# IED_GR_Module_Rev_01.net
KiCad netlist of a schematic drawn in EAGLE
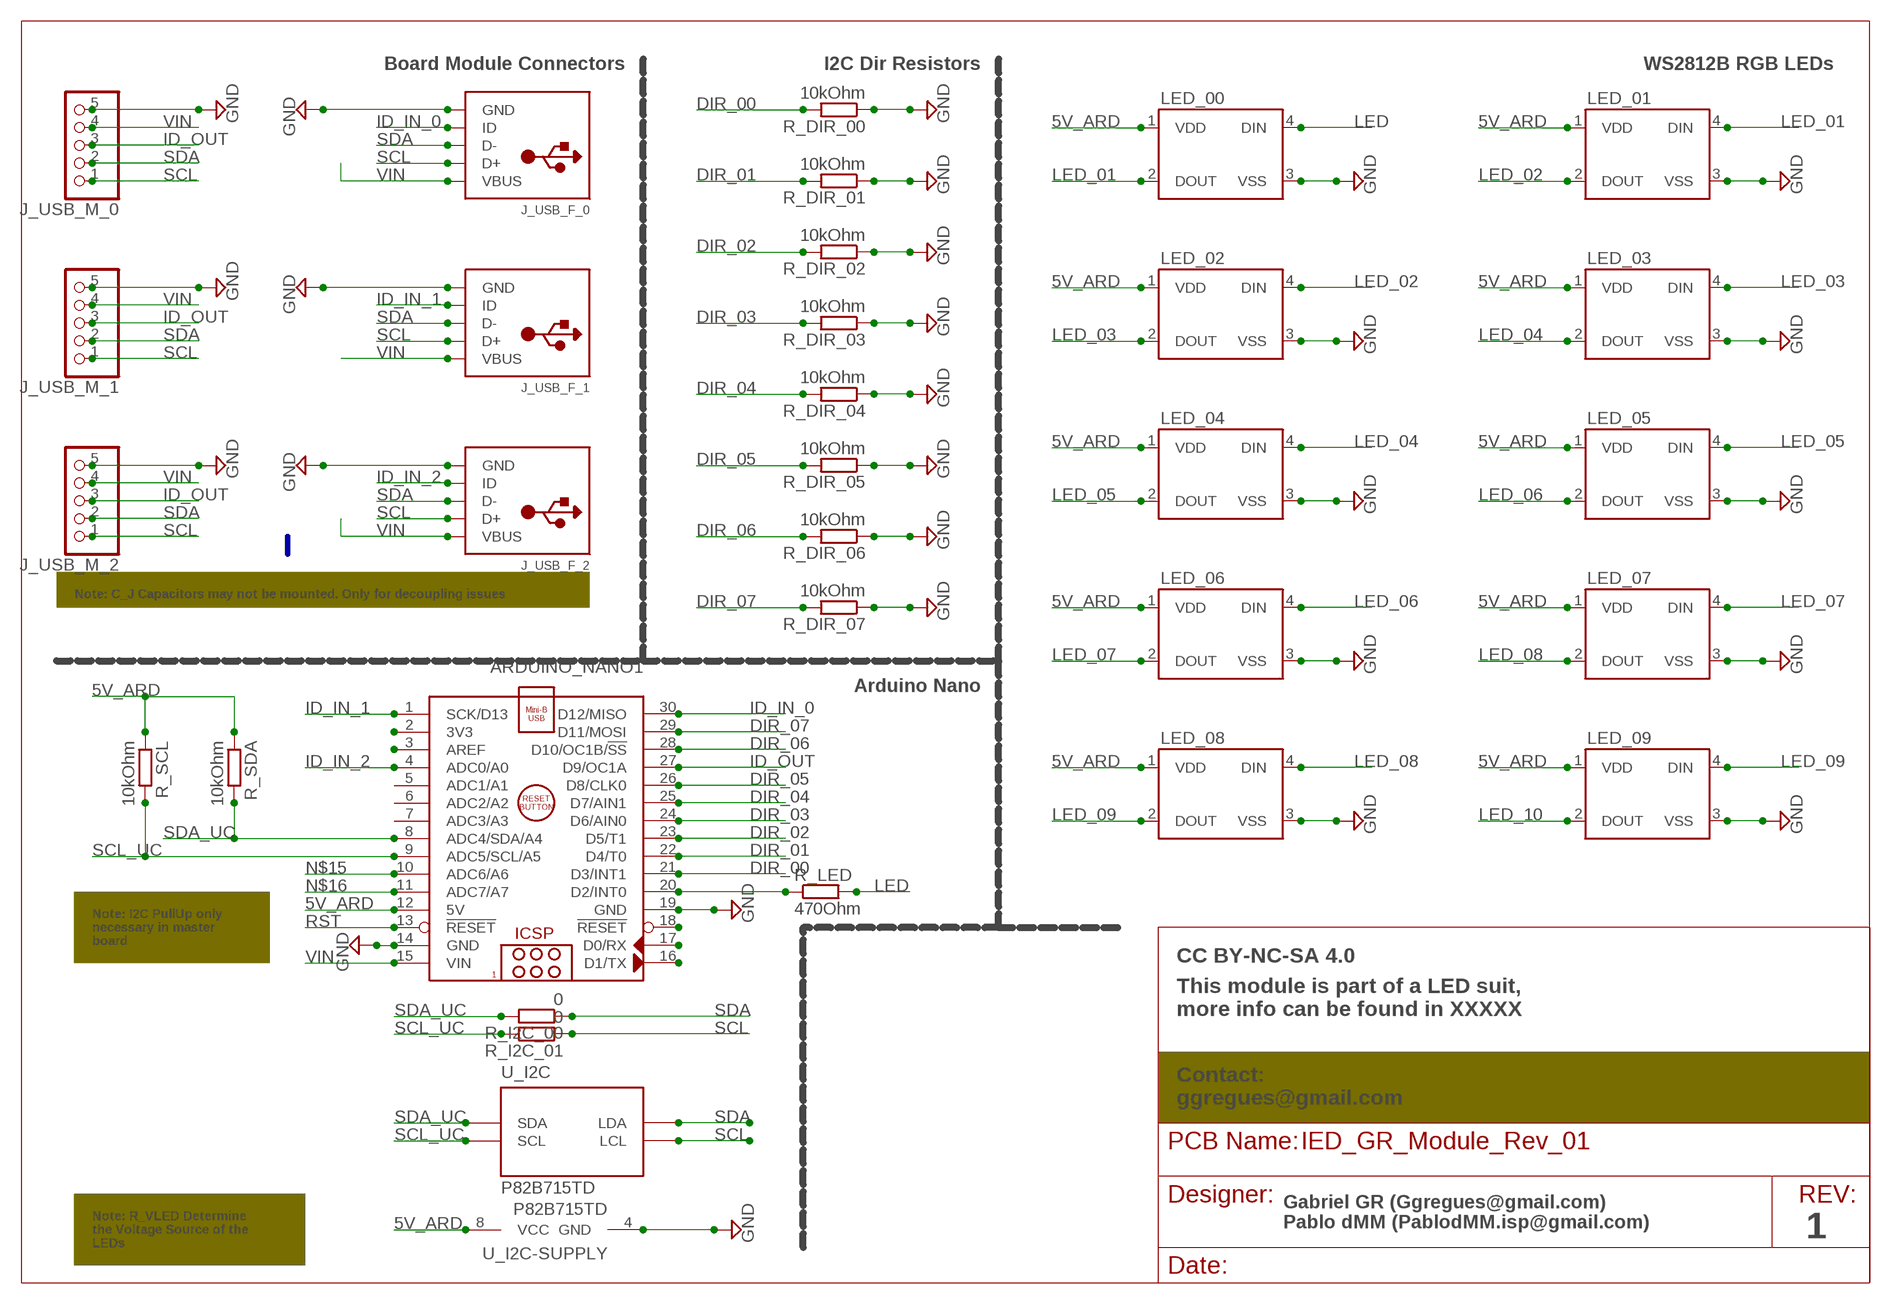
[diagram p0: schematic, sheet 1]

(export (version "E")
  (design (tool "Eeschema 10.0.6"))
  (components
    (comp (ref "ARDUINO_NANO1")
      (value "ARDUINO_NANO")
      (footprint "eagle-import:ARDUINO_NANO")
      (libsource (lib "eagle-import") (part "ARDUINO_NANO"))
    )
    (comp (ref "J_USB_F_0")
      (value "USBTHM")
      (footprint "eagle-import:USB-MINIB-THM")
      (libsource (lib "eagle-import") (part "USBTHM"))
    )
    (comp (ref "J_USB_F_1")
      (value "USBTHM")
      (footprint "eagle-import:USB-MINIB-THM")
      (libsource (lib "eagle-import") (part "USBTHM"))
    )
    (comp (ref "J_USB_F_2")
      (value "USBTHM")
      (footprint "eagle-import:USB-MINIB-THM")
      (libsource (lib "eagle-import") (part "USBTHM"))
    )
    (comp (ref "J_USB_M_0")
      (value "HEADER-1X51.27MM")
      (footprint "eagle-import:1X05_1.27MM")
      (libsource (lib "eagle-import") (part "HEADER-1X51.27MM"))
    )
    (comp (ref "J_USB_M_1")
      (value "HEADER-1X51.27MM")
      (footprint "eagle-import:1X05_1.27MM")
      (libsource (lib "eagle-import") (part "HEADER-1X51.27MM"))
    )
    (comp (ref "J_USB_M_2")
      (value "HEADER-1X51.27MM")
      (footprint "eagle-import:1X05_1.27MM")
      (libsource (lib "eagle-import") (part "HEADER-1X51.27MM"))
    )
    (comp (ref "LED_00")
      (value "WS2812B")
      (footprint "eagle-import:WS2812B")
      (libsource (lib "eagle-import") (part "WS2812B"))
    )
    (comp (ref "LED_01")
      (value "WS2812B")
      (footprint "eagle-import:WS2812B")
      (libsource (lib "eagle-import") (part "WS2812B"))
    )
    (comp (ref "LED_02")
      (value "WS2812B")
      (footprint "eagle-import:WS2812B")
      (libsource (lib "eagle-import") (part "WS2812B"))
    )
    (comp (ref "LED_03")
      (value "WS2812B")
      (footprint "eagle-import:WS2812B")
      (libsource (lib "eagle-import") (part "WS2812B"))
    )
    (comp (ref "LED_04")
      (value "WS2812B")
      (footprint "eagle-import:WS2812B")
      (libsource (lib "eagle-import") (part "WS2812B"))
    )
    (comp (ref "LED_05")
      (value "WS2812B")
      (footprint "eagle-import:WS2812B")
      (libsource (lib "eagle-import") (part "WS2812B"))
    )
    (comp (ref "LED_06")
      (value "WS2812B")
      (footprint "eagle-import:WS2812B")
      (libsource (lib "eagle-import") (part "WS2812B"))
    )
    (comp (ref "LED_07")
      (value "WS2812B")
      (footprint "eagle-import:WS2812B")
      (libsource (lib "eagle-import") (part "WS2812B"))
    )
    (comp (ref "LED_08")
      (value "WS2812B")
      (footprint "eagle-import:WS2812B")
      (libsource (lib "eagle-import") (part "WS2812B"))
    )
    (comp (ref "LED_09")
      (value "WS2812B")
      (footprint "eagle-import:WS2812B")
      (libsource (lib "eagle-import") (part "WS2812B"))
    )
    (comp (ref "R_DIR_00")
      (value "10kOhm")
      (footprint "eagle-import:R1206")
      (libsource (lib "eagle-import") (part "R-EU_R1206"))
    )
    (comp (ref "R_DIR_01")
      (value "10kOhm")
      (footprint "eagle-import:R1206")
      (libsource (lib "eagle-import") (part "R-EU_R1206"))
    )
    (comp (ref "R_DIR_02")
      (value "10kOhm")
      (footprint "eagle-import:R1206")
      (libsource (lib "eagle-import") (part "R-EU_R1206"))
    )
    (comp (ref "R_DIR_03")
      (value "10kOhm")
      (footprint "eagle-import:R1206")
      (libsource (lib "eagle-import") (part "R-EU_R1206"))
    )
    (comp (ref "R_DIR_04")
      (value "10kOhm")
      (footprint "eagle-import:R1206")
      (libsource (lib "eagle-import") (part "R-EU_R1206"))
    )
    (comp (ref "R_DIR_05")
      (value "10kOhm")
      (footprint "eagle-import:R1206")
      (libsource (lib "eagle-import") (part "R-EU_R1206"))
    )
    (comp (ref "R_DIR_06")
      (value "10kOhm")
      (footprint "eagle-import:R1206")
      (libsource (lib "eagle-import") (part "R-EU_R1206"))
    )
    (comp (ref "R_DIR_07")
      (value "10kOhm")
      (footprint "eagle-import:R1206")
      (libsource (lib "eagle-import") (part "R-EU_R1206"))
    )
    (comp (ref "R_I2C_00")
      (value "0")
      (footprint "eagle-import:R1206")
      (libsource (lib "eagle-import") (part "R-EU_R1206"))
    )
    (comp (ref "R_I2C_01")
      (value "0")
      (footprint "eagle-import:R1206")
      (libsource (lib "eagle-import") (part "R-EU_R1206"))
    )
    (comp (ref "R_LED")
      (value "470Ohm")
      (footprint "eagle-import:R1206")
      (libsource (lib "eagle-import") (part "R-EU_R1206"))
    )
    (comp (ref "R_SCL")
      (value "10kOhm")
      (footprint "eagle-import:R1206")
      (libsource (lib "eagle-import") (part "R-EU_R1206"))
    )
    (comp (ref "R_SDA")
      (value "10kOhm")
      (footprint "eagle-import:R1206")
      (libsource (lib "eagle-import") (part "R-EU_R1206"))
    )
    (comp (ref "U_I2C")
      (value "P82B715TD")
      (footprint "eagle-import:SOIC-8")
      (fields (field (name "MANUFACTURER") "NXP Semiconductors") (field (name "PART_NUMBER") "P82B715TD,118"))
      (libsource (lib "eagle-import") (part "P82B715?TD"))
    )
  )
  (nets
    (net (code "1") (name "/5V_ARD") (class "Default")
      (node (ref "ARDUINO_NANO1") (pin "12") (pinfunction "5V_12") (pintype "power_in"))
      (node (ref "LED_00") (pin "1") (pinfunction "VDD_1") (pintype "power_in"))
      (node (ref "LED_01") (pin "1") (pinfunction "VDD_1") (pintype "power_in"))
      (node (ref "LED_02") (pin "1") (pinfunction "VDD_1") (pintype "power_in"))
      (node (ref "LED_03") (pin "1") (pinfunction "VDD_1") (pintype "power_in"))
      (node (ref "LED_04") (pin "1") (pinfunction "VDD_1") (pintype "power_in"))
      (node (ref "LED_05") (pin "1") (pinfunction "VDD_1") (pintype "power_in"))
      (node (ref "LED_06") (pin "1") (pinfunction "VDD_1") (pintype "power_in"))
      (node (ref "LED_07") (pin "1") (pinfunction "VDD_1") (pintype "power_in"))
      (node (ref "LED_08") (pin "1") (pinfunction "VDD_1") (pintype "power_in"))
      (node (ref "LED_09") (pin "1") (pinfunction "VDD_1") (pintype "power_in"))
      (node (ref "R_SCL") (pin "1") (pinfunction "1_1") (pintype "passive"))
      (node (ref "R_SDA") (pin "1") (pinfunction "1_1") (pintype "passive"))
      (node (ref "U_I2C") (pin "8") (pinfunction "VCC_8") (pintype "bidirectional"))
    )
    (net (code "2") (name "/DIR_00") (class "Default")
      (node (ref "ARDUINO_NANO1") (pin "21") (pinfunction "D3/INT1_21") (pintype "bidirectional"))
      (node (ref "R_DIR_00") (pin "2") (pinfunction "2_2") (pintype "passive"))
    )
    (net (code "3") (name "/DIR_01") (class "Default")
      (node (ref "ARDUINO_NANO1") (pin "22") (pinfunction "D4/T0_22") (pintype "bidirectional"))
      (node (ref "R_DIR_01") (pin "2") (pinfunction "2_2") (pintype "passive"))
    )
    (net (code "4") (name "/DIR_02") (class "Default")
      (node (ref "ARDUINO_NANO1") (pin "23") (pinfunction "D5/T1_23") (pintype "bidirectional"))
      (node (ref "R_DIR_02") (pin "2") (pinfunction "2_2") (pintype "passive"))
    )
    (net (code "5") (name "/DIR_03") (class "Default")
      (node (ref "ARDUINO_NANO1") (pin "24") (pinfunction "D6/AIN0_24") (pintype "bidirectional"))
      (node (ref "R_DIR_03") (pin "2") (pinfunction "2_2") (pintype "passive"))
    )
    (net (code "6") (name "/DIR_04") (class "Default")
      (node (ref "ARDUINO_NANO1") (pin "25") (pinfunction "D7/AIN1_25") (pintype "bidirectional"))
      (node (ref "R_DIR_04") (pin "2") (pinfunction "2_2") (pintype "passive"))
    )
    (net (code "7") (name "/DIR_05") (class "Default")
      (node (ref "ARDUINO_NANO1") (pin "26") (pinfunction "D8/CLK0_26") (pintype "bidirectional"))
      (node (ref "R_DIR_05") (pin "2") (pinfunction "2_2") (pintype "passive"))
    )
    (net (code "8") (name "/DIR_06") (class "Default")
      (node (ref "ARDUINO_NANO1") (pin "28") (pinfunction "D10/OC1B/~{SS}_28") (pintype "bidirectional"))
      (node (ref "R_DIR_06") (pin "2") (pinfunction "2_2") (pintype "passive"))
    )
    (net (code "9") (name "/DIR_07") (class "Default")
      (node (ref "ARDUINO_NANO1") (pin "29") (pinfunction "D11/MOSI_29") (pintype "bidirectional"))
      (node (ref "R_DIR_07") (pin "2") (pinfunction "2_2") (pintype "passive"))
    )
    (net (code "10") (name "/ID_IN_0") (class "Default")
      (node (ref "ARDUINO_NANO1") (pin "30") (pinfunction "D12/MISO_30") (pintype "bidirectional"))
      (node (ref "J_USB_F_0") (pin "ID") (pinfunction "ID_ID") (pintype "bidirectional"))
    )
    (net (code "11") (name "/ID_IN_1") (class "Default")
      (node (ref "ARDUINO_NANO1") (pin "1") (pinfunction "SCK/D13_1") (pintype "bidirectional"))
      (node (ref "J_USB_F_1") (pin "ID") (pinfunction "ID_ID") (pintype "bidirectional"))
    )
    (net (code "12") (name "/ID_IN_2") (class "Default")
      (node (ref "ARDUINO_NANO1") (pin "4") (pinfunction "ADC0/A0_4") (pintype "bidirectional"))
      (node (ref "J_USB_F_2") (pin "ID") (pinfunction "ID_ID") (pintype "bidirectional"))
    )
    (net (code "13") (name "/ID_OUT") (class "Default")
      (node (ref "ARDUINO_NANO1") (pin "27") (pinfunction "D9/OC1A_27") (pintype "bidirectional"))
      (node (ref "J_USB_M_0") (pin "3") (pinfunction "3_3") (pintype "passive"))
      (node (ref "J_USB_M_1") (pin "3") (pinfunction "3_3") (pintype "passive"))
      (node (ref "J_USB_M_2") (pin "3") (pinfunction "3_3") (pintype "passive"))
    )
    (net (code "14") (name "/LED") (class "Default")
      (node (ref "LED_00") (pin "4") (pinfunction "DIN_4") (pintype "input"))
      (node (ref "R_LED") (pin "2") (pinfunction "2_2") (pintype "passive"))
    )
    (net (code "15") (name "/LED_01") (class "Default")
      (node (ref "LED_00") (pin "2") (pinfunction "DOUT_2") (pintype "output"))
      (node (ref "LED_01") (pin "4") (pinfunction "DIN_4") (pintype "input"))
    )
    (net (code "16") (name "/LED_02") (class "Default")
      (node (ref "LED_01") (pin "2") (pinfunction "DOUT_2") (pintype "output"))
      (node (ref "LED_02") (pin "4") (pinfunction "DIN_4") (pintype "input"))
    )
    (net (code "17") (name "/LED_03") (class "Default")
      (node (ref "LED_02") (pin "2") (pinfunction "DOUT_2") (pintype "output"))
      (node (ref "LED_03") (pin "4") (pinfunction "DIN_4") (pintype "input"))
    )
    (net (code "18") (name "/LED_04") (class "Default")
      (node (ref "LED_03") (pin "2") (pinfunction "DOUT_2") (pintype "output"))
      (node (ref "LED_04") (pin "4") (pinfunction "DIN_4") (pintype "input"))
    )
    (net (code "19") (name "/LED_05") (class "Default")
      (node (ref "LED_04") (pin "2") (pinfunction "DOUT_2") (pintype "output"))
      (node (ref "LED_05") (pin "4") (pinfunction "DIN_4") (pintype "input"))
    )
    (net (code "20") (name "/LED_06") (class "Default")
      (node (ref "LED_05") (pin "2") (pinfunction "DOUT_2") (pintype "output"))
      (node (ref "LED_06") (pin "4") (pinfunction "DIN_4") (pintype "input"))
    )
    (net (code "21") (name "/LED_07") (class "Default")
      (node (ref "LED_06") (pin "2") (pinfunction "DOUT_2") (pintype "output"))
      (node (ref "LED_07") (pin "4") (pinfunction "DIN_4") (pintype "input"))
    )
    (net (code "22") (name "/LED_08") (class "Default")
      (node (ref "LED_07") (pin "2") (pinfunction "DOUT_2") (pintype "output"))
      (node (ref "LED_08") (pin "4") (pinfunction "DIN_4") (pintype "input"))
    )
    (net (code "23") (name "/LED_09") (class "Default")
      (node (ref "LED_08") (pin "2") (pinfunction "DOUT_2") (pintype "output"))
      (node (ref "LED_09") (pin "4") (pinfunction "DIN_4") (pintype "input"))
    )
    (net (code "24") (name "/LED_10") (class "Default")
      (node (ref "LED_09") (pin "2") (pinfunction "DOUT_2") (pintype "output"))
    )
    (net (code "25") (name "/N$15") (class "Default")
      (node (ref "ARDUINO_NANO1") (pin "10") (pinfunction "ADC6/A6_10") (pintype "bidirectional"))
    )
    (net (code "26") (name "/N$16") (class "Default")
      (node (ref "ARDUINO_NANO1") (pin "11") (pinfunction "ADC7/A7_11") (pintype "bidirectional"))
    )
    (net (code "27") (name "/RST") (class "Default")
      (node (ref "ARDUINO_NANO1") (pin "13") (pinfunction "~{RESET}_13") (pintype "input"))
    )
    (net (code "28") (name "/SCL") (class "Default")
      (node (ref "J_USB_F_0") (pin "D+") (pinfunction "D+_D+") (pintype "bidirectional"))
      (node (ref "J_USB_F_1") (pin "D+") (pinfunction "D+_D+") (pintype "bidirectional"))
      (node (ref "J_USB_F_2") (pin "D+") (pinfunction "D+_D+") (pintype "bidirectional"))
      (node (ref "J_USB_M_0") (pin "1") (pinfunction "1_1") (pintype "passive"))
      (node (ref "J_USB_M_1") (pin "1") (pinfunction "1_1") (pintype "passive"))
      (node (ref "J_USB_M_2") (pin "1") (pinfunction "1_1") (pintype "passive"))
      (node (ref "R_I2C_01") (pin "1") (pinfunction "1_1") (pintype "passive"))
      (node (ref "U_I2C") (pin "2") (pinfunction "LCL_2") (pintype "bidirectional"))
    )
    (net (code "29") (name "/SCL_UC") (class "Default")
      (node (ref "ARDUINO_NANO1") (pin "9") (pinfunction "ADC5/SCL/A5_9") (pintype "bidirectional"))
      (node (ref "R_I2C_01") (pin "2") (pinfunction "2_2") (pintype "passive"))
      (node (ref "R_SCL") (pin "2") (pinfunction "2_2") (pintype "passive"))
      (node (ref "U_I2C") (pin "3") (pinfunction "SCL_3") (pintype "bidirectional"))
    )
    (net (code "30") (name "/SDA") (class "Default")
      (node (ref "J_USB_F_0") (pin "D-") (pinfunction "D-_D-") (pintype "bidirectional"))
      (node (ref "J_USB_F_1") (pin "D-") (pinfunction "D-_D-") (pintype "bidirectional"))
      (node (ref "J_USB_F_2") (pin "D-") (pinfunction "D-_D-") (pintype "bidirectional"))
      (node (ref "J_USB_M_0") (pin "2") (pinfunction "2_2") (pintype "passive"))
      (node (ref "J_USB_M_1") (pin "2") (pinfunction "2_2") (pintype "passive"))
      (node (ref "J_USB_M_2") (pin "2") (pinfunction "2_2") (pintype "passive"))
      (node (ref "R_I2C_00") (pin "1") (pinfunction "1_1") (pintype "passive"))
      (node (ref "U_I2C") (pin "7") (pinfunction "LDA_7") (pintype "bidirectional"))
    )
    (net (code "31") (name "/SDA_UC") (class "Default")
      (node (ref "ARDUINO_NANO1") (pin "8") (pinfunction "ADC4/SDA/A4_8") (pintype "bidirectional"))
      (node (ref "R_I2C_00") (pin "2") (pinfunction "2_2") (pintype "passive"))
      (node (ref "R_SDA") (pin "2") (pinfunction "2_2") (pintype "passive"))
      (node (ref "U_I2C") (pin "6") (pinfunction "SDA_6") (pintype "bidirectional"))
    )
    (net (code "32") (name "/VIN") (class "Default")
      (node (ref "ARDUINO_NANO1") (pin "15") (pinfunction "VIN_15") (pintype "power_in"))
      (node (ref "J_USB_F_0") (pin "VBUS") (pinfunction "VBUS_VBUS") (pintype "power_in"))
      (node (ref "J_USB_F_1") (pin "VBUS") (pinfunction "VBUS_VBUS") (pintype "power_in"))
      (node (ref "J_USB_F_2") (pin "VBUS") (pinfunction "VBUS_VBUS") (pintype "power_in"))
      (node (ref "J_USB_M_0") (pin "4") (pinfunction "4_4") (pintype "passive"))
      (node (ref "J_USB_M_1") (pin "4") (pinfunction "4_4") (pintype "passive"))
      (node (ref "J_USB_M_2") (pin "4") (pinfunction "4_4") (pintype "passive"))
    )
    (net (code "33") (name "GND") (class "Default")
      (node (ref "ARDUINO_NANO1") (pin "14") (pinfunction "GND_14") (pintype "power_in"))
      (node (ref "ARDUINO_NANO1") (pin "19") (pinfunction "GND_19") (pintype "power_in"))
      (node (ref "J_USB_F_0") (pin "GND") (pinfunction "GND_GND") (pintype "power_in"))
      (node (ref "J_USB_F_1") (pin "GND") (pinfunction "GND_GND") (pintype "power_in"))
      (node (ref "J_USB_F_2") (pin "GND") (pinfunction "GND_GND") (pintype "power_in"))
      (node (ref "J_USB_M_0") (pin "5") (pinfunction "5_5") (pintype "passive"))
      (node (ref "J_USB_M_1") (pin "5") (pinfunction "5_5") (pintype "passive"))
      (node (ref "J_USB_M_2") (pin "5") (pinfunction "5_5") (pintype "passive"))
      (node (ref "LED_00") (pin "3") (pinfunction "VSS_3") (pintype "power_in"))
      (node (ref "LED_01") (pin "3") (pinfunction "VSS_3") (pintype "power_in"))
      (node (ref "LED_02") (pin "3") (pinfunction "VSS_3") (pintype "power_in"))
      (node (ref "LED_03") (pin "3") (pinfunction "VSS_3") (pintype "power_in"))
      (node (ref "LED_04") (pin "3") (pinfunction "VSS_3") (pintype "power_in"))
      (node (ref "LED_05") (pin "3") (pinfunction "VSS_3") (pintype "power_in"))
      (node (ref "LED_06") (pin "3") (pinfunction "VSS_3") (pintype "power_in"))
      (node (ref "LED_07") (pin "3") (pinfunction "VSS_3") (pintype "power_in"))
      (node (ref "LED_08") (pin "3") (pinfunction "VSS_3") (pintype "power_in"))
      (node (ref "LED_09") (pin "3") (pinfunction "VSS_3") (pintype "power_in"))
      (node (ref "R_DIR_00") (pin "1") (pinfunction "1_1") (pintype "passive"))
      (node (ref "R_DIR_01") (pin "1") (pinfunction "1_1") (pintype "passive"))
      (node (ref "R_DIR_02") (pin "1") (pinfunction "1_1") (pintype "passive"))
      (node (ref "R_DIR_03") (pin "1") (pinfunction "1_1") (pintype "passive"))
      (node (ref "R_DIR_04") (pin "1") (pinfunction "1_1") (pintype "passive"))
      (node (ref "R_DIR_05") (pin "1") (pinfunction "1_1") (pintype "passive"))
      (node (ref "R_DIR_06") (pin "1") (pinfunction "1_1") (pintype "passive"))
      (node (ref "R_DIR_07") (pin "1") (pinfunction "1_1") (pintype "passive"))
      (node (ref "U_I2C") (pin "4") (pinfunction "GND_4") (pintype "bidirectional"))
    )
    (net (code "34") (name "Net-(ARDUINO_NANO1-D2{slash}INT0)") (class "Default")
      (node (ref "ARDUINO_NANO1") (pin "20") (pinfunction "D2/INT0_20") (pintype "bidirectional"))
      (node (ref "R_LED") (pin "1") (pinfunction "1_1") (pintype "passive"))
    )
    (net (code "35") (name "unconnected-(ARDUINO_NANO1-3V3-Pad2)") (class "Default")
      (node (ref "ARDUINO_NANO1") (pin "2") (pinfunction "3V3_2") (pintype "output"))
    )
    (net (code "36") (name "unconnected-(ARDUINO_NANO1-ADC1{slash}A1-Pad5)") (class "Default")
      (node (ref "ARDUINO_NANO1") (pin "5") (pinfunction "ADC1/A1_5") (pintype "bidirectional"))
    )
    (net (code "37") (name "unconnected-(ARDUINO_NANO1-ADC2{slash}A2-Pad6)") (class "Default")
      (node (ref "ARDUINO_NANO1") (pin "6") (pinfunction "ADC2/A2_6") (pintype "bidirectional"))
    )
    (net (code "38") (name "unconnected-(ARDUINO_NANO1-ADC3{slash}A3-Pad7)") (class "Default")
      (node (ref "ARDUINO_NANO1") (pin "7") (pinfunction "ADC3/A3_7") (pintype "bidirectional"))
    )
    (net (code "39") (name "unconnected-(ARDUINO_NANO1-AREF-Pad3)") (class "Default")
      (node (ref "ARDUINO_NANO1") (pin "3") (pinfunction "AREF_3") (pintype "input"))
    )
    (net (code "40") (name "unconnected-(ARDUINO_NANO1-D0{slash}RX-Pad17)") (class "Default")
      (node (ref "ARDUINO_NANO1") (pin "17") (pinfunction "D0/RX_17") (pintype "bidirectional"))
    )
    (net (code "41") (name "unconnected-(ARDUINO_NANO1-D1{slash}TX-Pad16)") (class "Default")
      (node (ref "ARDUINO_NANO1") (pin "16") (pinfunction "D1/TX_16") (pintype "bidirectional"))
    )
    (net (code "42") (name "unconnected-(ARDUINO_NANO1-~{RESET}-Pad18)") (class "Default")
      (node (ref "ARDUINO_NANO1") (pin "18") (pinfunction "~{RESET}_18") (pintype "input"))
    )
  )
)
